# PMIC-MX8M.net
KiCad netlist of a schematic drawn in Altium Designer
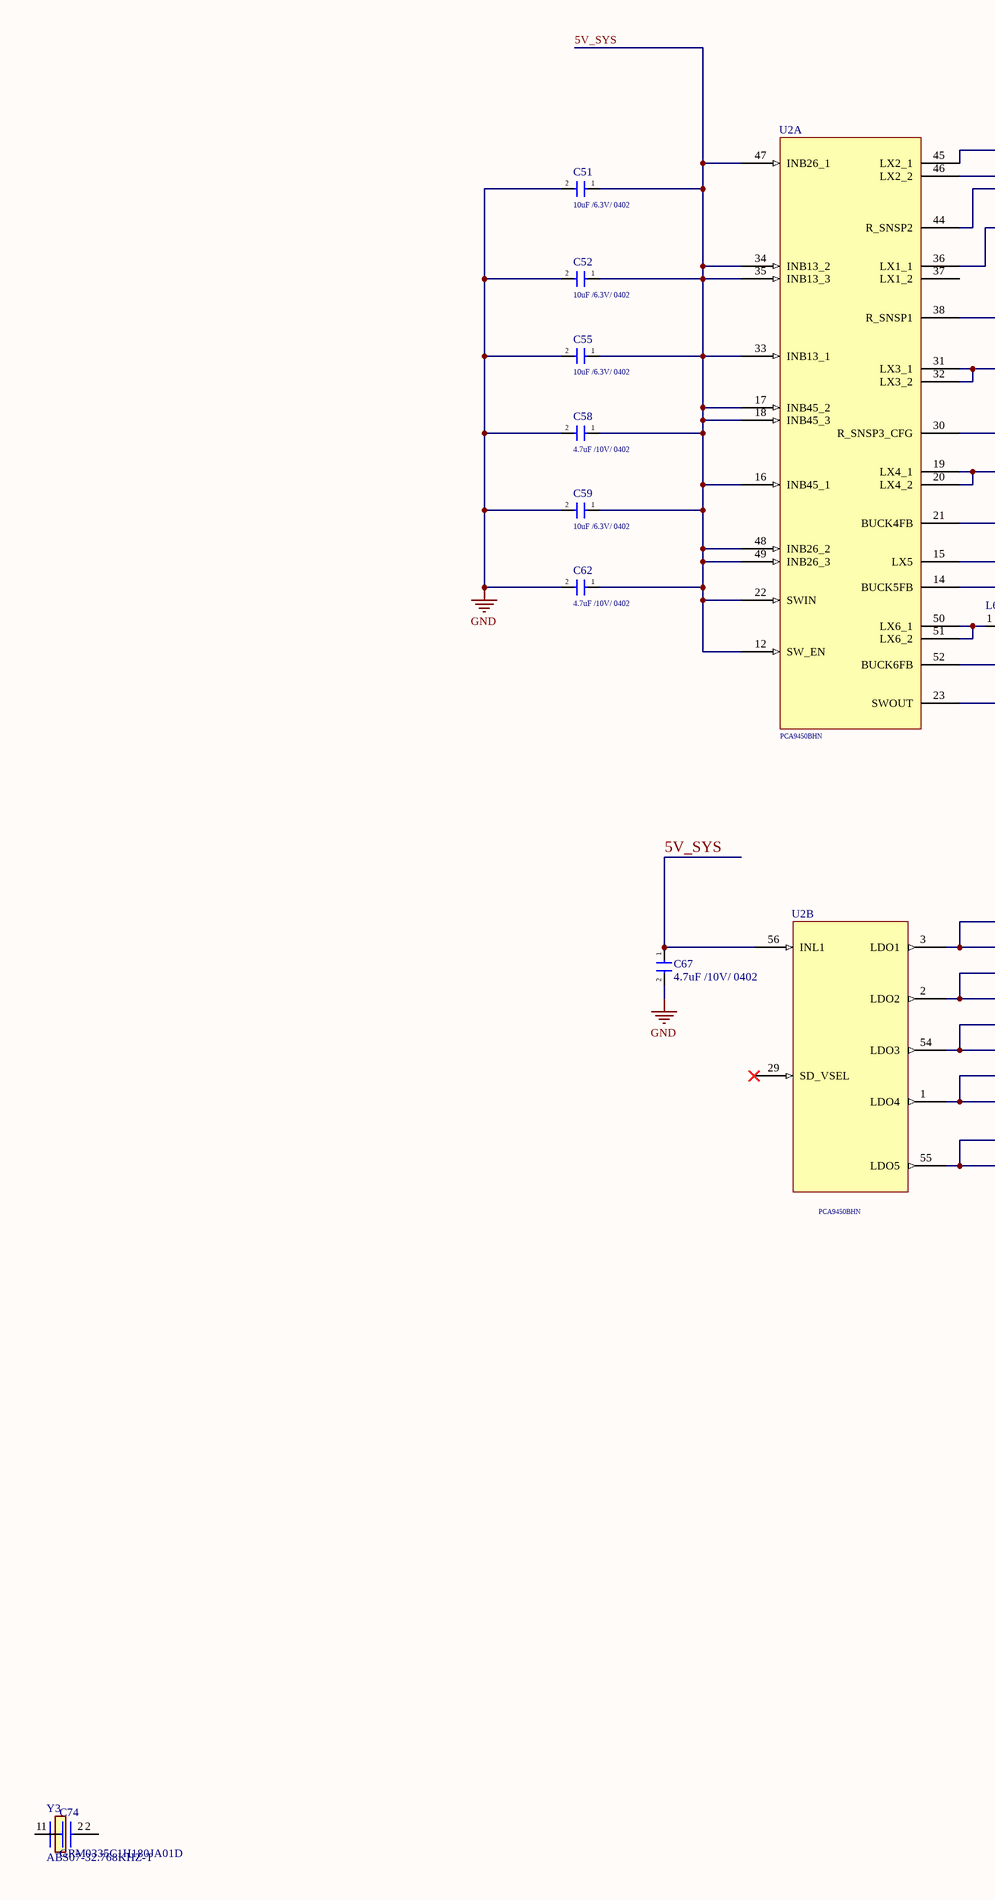
[diagram p0: PMIC-MX8M.SchDoc, left]
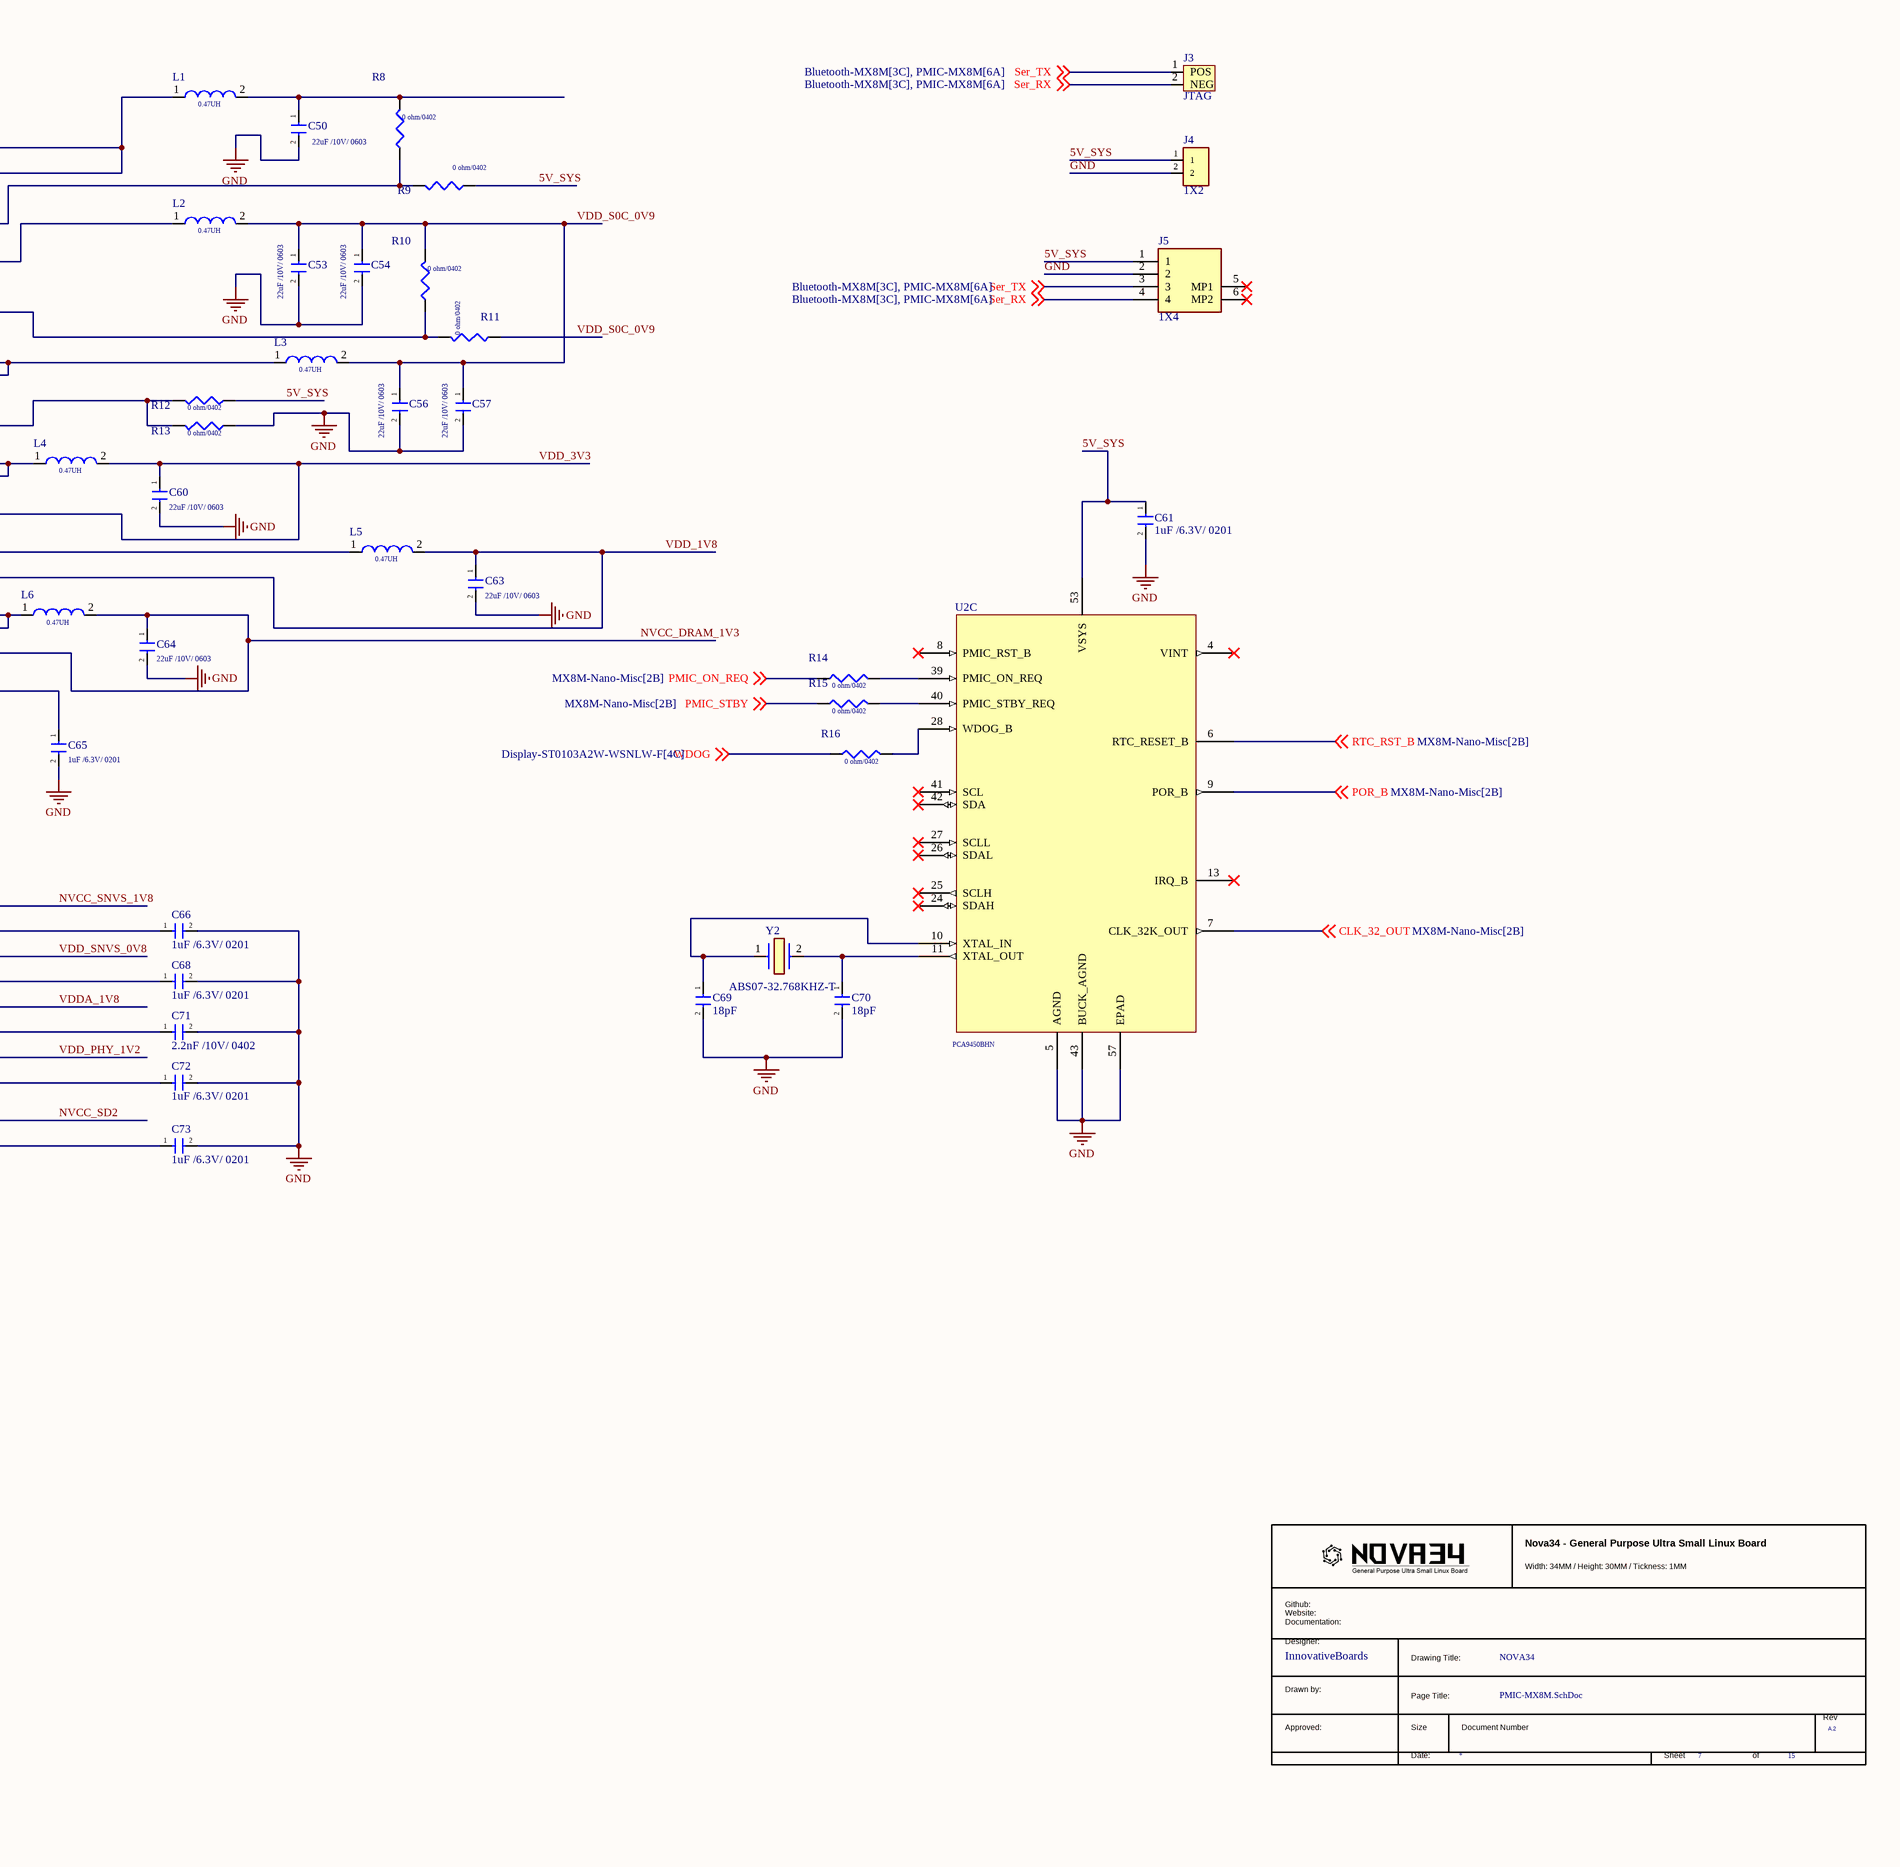
[diagram p1: PMIC-MX8M.SchDoc, right]

(export (version "E")
  (design (tool "Eeschema 10.0.6"))
  (components
    (comp (ref "C50")
      (value "22uF /10V/ 0603")
      (footprint "GRM18x")
      (description "Multilayer Ceramic Capacitors MLCC - SMD/SMT 22 uF 10 VDC 20% 0603 X5R")
      (fields
        (field (name "MANUFACTURER_PART_NUMBER") "GRM187R61A226ME15D")
        (field (name "MOUSER PART NUMBER") "81-GRM187R61A226ME5D")
      )
      (libsource (lib "Nova_SCHLIB") (part "GRM187R61A226ME15D"))
    )
    (comp (ref "C51")
      (value "10uF /6.3V/ 0402")
      (footprint "CAPC1005X65N")
      (description "Multilayer Ceramic Capacitors MLCC - SMD/SMT 10 uF 6.3 VDC 20% 0402 X5R")
      (fields
        (field (name "MANUFACTURER_PART_NUMBER") "GRM155R60J106ME15D")
        (field (name "MOUSER PART NUMBER") "81-GRM155R60J106ME5D")
      )
      (libsource (lib "Nova_SCHLIB") (part "GRM155R60J106ME15D"))
    )
    (comp (ref "C52")
      (value "10uF /6.3V/ 0402")
      (footprint "CAPC1005X65N")
      (description "Multilayer Ceramic Capacitors MLCC - SMD/SMT 10 uF 6.3 VDC 20% 0402 X5R")
      (fields
        (field (name "MANUFACTURER_PART_NUMBER") "GRM155R60J106ME15D")
        (field (name "MOUSER PART NUMBER") "81-GRM155R60J106ME5D")
      )
      (libsource (lib "Nova_SCHLIB") (part "GRM155R60J106ME15D"))
    )
    (comp (ref "C53")
      (value "22uF /10V/ 0603")
      (footprint "GRM18x")
      (description "Multilayer Ceramic Capacitors MLCC - SMD/SMT 22 uF 10 VDC 20% 0603 X5R")
      (fields
        (field (name "MANUFACTURER_PART_NUMBER") "GRM187R61A226ME15D")
        (field (name "MOUSER PART NUMBER") "81-GRM187R61A226ME5D")
      )
      (libsource (lib "Nova_SCHLIB") (part "GRM187R61A226ME15D"))
    )
    (comp (ref "C54")
      (value "22uF /10V/ 0603")
      (footprint "GRM18x")
      (description "Multilayer Ceramic Capacitors MLCC - SMD/SMT 22 uF 10 VDC 20% 0603 X5R")
      (fields
        (field (name "MANUFACTURER_PART_NUMBER") "GRM187R61A226ME15D")
        (field (name "MOUSER PART NUMBER") "81-GRM187R61A226ME5D")
      )
      (libsource (lib "Nova_SCHLIB") (part "GRM187R61A226ME15D"))
    )
    (comp (ref "C55")
      (value "10uF /6.3V/ 0402")
      (footprint "CAPC1005X65N")
      (description "Multilayer Ceramic Capacitors MLCC - SMD/SMT 10 uF 6.3 VDC 20% 0402 X5R")
      (fields
        (field (name "MANUFACTURER_PART_NUMBER") "GRM155R60J106ME15D")
        (field (name "MOUSER PART NUMBER") "81-GRM155R60J106ME5D")
      )
      (libsource (lib "Nova_SCHLIB") (part "GRM155R60J106ME15D"))
    )
    (comp (ref "C56")
      (value "22uF /10V/ 0603")
      (footprint "GRM18x")
      (description "Multilayer Ceramic Capacitors MLCC - SMD/SMT 22 uF 10 VDC 20% 0603 X5R")
      (fields
        (field (name "MANUFACTURER_PART_NUMBER") "GRM187R61A226ME15D")
        (field (name "MOUSER PART NUMBER") "81-GRM187R61A226ME5D")
      )
      (libsource (lib "Nova_SCHLIB") (part "GRM187R61A226ME15D"))
    )
    (comp (ref "C57")
      (value "22uF /10V/ 0603")
      (footprint "GRM18x")
      (description "Multilayer Ceramic Capacitors MLCC - SMD/SMT 22 uF 10 VDC 20% 0603 X5R")
      (fields
        (field (name "MANUFACTURER_PART_NUMBER") "GRM187R61A226ME15D")
        (field (name "MOUSER PART NUMBER") "81-GRM187R61A226ME5D")
      )
      (libsource (lib "Nova_SCHLIB") (part "GRM187R61A226ME15D"))
    )
    (comp (ref "C58")
      (value "4.7uF /10V/ 0402")
      (footprint "CAPC1005X70N")
      (description "Multilayer Ceramic Capacitors MLCC - SMD/SMT 0402 X6S 4.7 F 20 10VDC AEC-Q200")
      (fields
        (field (name "MANUFACTURER_PART_NUMBER") "GRT155C81A475ME13J")
        (field (name "MOUSER PART NUMBER") "81-GRT155C81A475ME3J")
      )
      (libsource (lib "Nova_SCHLIB") (part "GRT155C81A475ME13J"))
    )
    (comp (ref "C59")
      (value "10uF /6.3V/ 0402")
      (footprint "CAPC1005X65N")
      (description "Multilayer Ceramic Capacitors MLCC - SMD/SMT 10 uF 6.3 VDC 20% 0402 X5R")
      (fields
        (field (name "MANUFACTURER_PART_NUMBER") "GRM155R60J106ME15D")
        (field (name "MOUSER PART NUMBER") "81-GRM155R60J106ME5D")
      )
      (libsource (lib "Nova_SCHLIB") (part "GRM155R60J106ME15D"))
    )
    (comp (ref "C60")
      (value "22uF /10V/ 0603")
      (footprint "GRM18x")
      (description "Multilayer Ceramic Capacitors MLCC - SMD/SMT 22 uF 10 VDC 20% 0603 X5R")
      (fields
        (field (name "MANUFACTURER_PART_NUMBER") "GRM187R61A226ME15D")
        (field (name "MOUSER PART NUMBER") "81-GRM187R61A226ME5D")
      )
      (libsource (lib "Nova_SCHLIB") (part "GRM187R61A226ME15D"))
    )
    (comp (ref "C61")
      (value "1uF /6.3V/ 0201")
      (footprint "GRM033D70J224ME01D")
      (description "Multilayer Ceramic Capacitors MLCC - SMD/SMT 1 uF 6.3 VDC 20% 0201 X6S")
      (fields
        (field (name "MANUFACTURER_PART_NUMBER") "GRM033C80J105ME05J")
        (field (name "MOUSER PART NUMBER") "81-GRM033C80J105ME5J")
      )
      (libsource (lib "Nova_SCHLIB") (part "GRM033C80J105ME05J"))
    )
    (comp (ref "C62")
      (value "4.7uF /10V/ 0402")
      (footprint "CAPC1005X70N")
      (description "Multilayer Ceramic Capacitors MLCC - SMD/SMT 0402 X6S 4.7 F 20 10VDC AEC-Q200")
      (fields
        (field (name "MANUFACTURER_PART_NUMBER") "GRT155C81A475ME13J")
        (field (name "MOUSER PART NUMBER") "81-GRT155C81A475ME3J")
      )
      (libsource (lib "Nova_SCHLIB") (part "GRT155C81A475ME13J"))
    )
    (comp (ref "C63")
      (value "22uF /10V/ 0603")
      (footprint "GRM18x")
      (description "Multilayer Ceramic Capacitors MLCC - SMD/SMT 22 uF 10 VDC 20% 0603 X5R")
      (fields
        (field (name "MANUFACTURER_PART_NUMBER") "GRM187R61A226ME15D")
        (field (name "MOUSER PART NUMBER") "81-GRM187R61A226ME5D")
      )
      (libsource (lib "Nova_SCHLIB") (part "GRM187R61A226ME15D"))
    )
    (comp (ref "C64")
      (value "22uF /10V/ 0603")
      (footprint "GRM18x")
      (description "Multilayer Ceramic Capacitors MLCC - SMD/SMT 22 uF 10 VDC 20% 0603 X5R")
      (fields
        (field (name "MANUFACTURER_PART_NUMBER") "GRM187R61A226ME15D")
        (field (name "MOUSER PART NUMBER") "81-GRM187R61A226ME5D")
      )
      (libsource (lib "Nova_SCHLIB") (part "GRM187R61A226ME15D"))
    )
    (comp (ref "C65")
      (value "1uF /6.3V/ 0201")
      (footprint "GRM033D70J224ME01D")
      (description "Multilayer Ceramic Capacitors MLCC - SMD/SMT 1 uF 6.3 VDC 20% 0201 X6S")
      (fields
        (field (name "MANUFACTURER_PART_NUMBER") "GRM033C80J105ME05J")
        (field (name "MOUSER PART NUMBER") "81-GRM033C80J105ME5J")
      )
      (libsource (lib "Nova_SCHLIB") (part "GRM033C80J105ME05J"))
    )
    (comp (ref "C66")
      (value "1uF /6.3V/ 0201")
      (footprint "GRM033D70J224ME01D")
      (description "Multilayer Ceramic Capacitors MLCC - SMD/SMT 1 uF 6.3 VDC 20% 0201 X6S")
      (fields
        (field (name "MANUFACTURER_PART_NUMBER") "GRM033C80J105ME05J")
        (field (name "MOUSER PART NUMBER") "81-GRM033C80J105ME5J")
      )
      (libsource (lib "Nova_SCHLIB") (part "GRM033C80J105ME05J"))
    )
    (comp (ref "C67")
      (value "4.7uF /10V/ 0402")
      (footprint "CAPC1005X70N")
      (description "Multilayer Ceramic Capacitors MLCC - SMD/SMT 0402 X6S 4.7 F 20 10VDC AEC-Q200")
      (fields
        (field (name "MANUFACTURER_PART_NUMBER") "GRT155C81A475ME13J")
        (field (name "MOUSER PART NUMBER") "81-GRT155C81A475ME3J")
      )
      (libsource (lib "Nova_SCHLIB") (part "GRT155C81A475ME13J"))
    )
    (comp (ref "C68")
      (value "1uF /6.3V/ 0201")
      (footprint "GRM033D70J224ME01D")
      (description "Multilayer Ceramic Capacitors MLCC - SMD/SMT 1 uF 6.3 VDC 20% 0201 X6S")
      (fields
        (field (name "MANUFACTURER_PART_NUMBER") "GRM033C80J105ME05J")
        (field (name "MOUSER PART NUMBER") "81-GRM033C80J105ME5J")
      )
      (libsource (lib "Nova_SCHLIB") (part "GRM033C80J105ME05J"))
    )
    (comp (ref "C69")
      (value "18pF")
      (footprint "CAPC0603X33N")
      (description "Capacitor")
      (fields
        (field (name "MANUFACTURER_PART_NUMBER") "GRM0335C1H180JA01D")
        (field (name "MOUSER PART NUMBER") "81-GRM0335C1H180JA1D")
      )
      (libsource (lib "Nova_SCHLIB") (part "GRM0335C1H180JA01D"))
    )
    (comp (ref "C70")
      (value "18pF")
      (footprint "CAPC0603X33N")
      (description "Capacitor")
      (fields
        (field (name "MANUFACTURER_PART_NUMBER") "GRM0335C1H180JA01D")
        (field (name "MOUSER PART NUMBER") "81-GRM0335C1H180JA1D")
      )
      (libsource (lib "Nova_SCHLIB") (part "GRM0335C1H180JA01D"))
    )
    (comp (ref "C71")
      (value "2.2nF /10V/ 0402")
      (footprint "CAPC1005X70N")
      (description "Multilayer Ceramic Capacitors MLCC - SMD/SMT 2200 pF 10 VDC 10% 0402 X5R")
      (fields
        (field (name "MANUFACTURER_PART_NUMBER") "GRM155R61A222KA01D")
        (field (name "MOUSER PART NUMBER") "81-GRM155R61A222KA1D")
      )
      (libsource (lib "Nova_SCHLIB") (part "GRM155R61A222KA01D"))
    )
    (comp (ref "C72")
      (value "1uF /6.3V/ 0201")
      (footprint "GRM033D70J224ME01D")
      (description "Multilayer Ceramic Capacitors MLCC - SMD/SMT 1 uF 6.3 VDC 20% 0201 X6S")
      (fields
        (field (name "MANUFACTURER_PART_NUMBER") "GRM033C80J105ME05J")
        (field (name "MOUSER PART NUMBER") "81-GRM033C80J105ME5J")
      )
      (libsource (lib "Nova_SCHLIB") (part "GRM033C80J105ME05J"))
    )
    (comp (ref "C73")
      (value "1uF /6.3V/ 0201")
      (footprint "GRM033D70J224ME01D")
      (description "Multilayer Ceramic Capacitors MLCC - SMD/SMT 1 uF 6.3 VDC 20% 0201 X6S")
      (fields
        (field (name "MANUFACTURER_PART_NUMBER") "GRM033C80J105ME05J")
        (field (name "MOUSER PART NUMBER") "81-GRM033C80J105ME5J")
      )
      (libsource (lib "Nova_SCHLIB") (part "GRM033C80J105ME05J"))
    )
    (comp (ref "C74")
      (value "GRM0335C1H180JA01D")
      (footprint "SamacSys:CAPC0603X33N")
      (description "Capacitor")
      (fields (field (name "MOUSER PART NUMBER") "81-GRM0335C1H180JA1D"))
      (libsource (lib "*") (part "GRM0335C1H180JA01D"))
    )
    (comp (ref "J3") (value "JTAG") (footprint "JTAG") (libsource (lib "Nova_SCHLIB") (part "JTAG")))
    (comp (ref "J4")
      (value "1X2")
      (footprint "HDRV2W64P0X254_1X2_508X254X838P")
      (description "Connector")
      (fields
        (field (name "MANUFACTURER_PART_NUMBER") "TSW-102-07-G-S-002")
        (field (name "MOUSER PART NUMBER") "200-TSW-10207GS002")
      )
      (libsource (lib "Nova_SCHLIB") (part "TSW-102-07-G-S-002"))
    )
    (comp (ref "J5")
      (value "1X4")
      (footprint "B4BZRSM4TFLFSN")
      (description "Connector")
      (fields (field (name "MANUFACTURER_PART_NUMBER") "B4B-ZR-SM4-TF(LF)(SN)"))
      (libsource (lib "Nova_SCHLIB") (part "B4B-ZR-SM4-TF_LF__SN_"))
    )
    (comp (ref "L1")
      (value "0.47UH")
      (footprint "IND_SPH2520")
      (description "470 nH Shielded Drum Core, Wirewound Inductor 4.1 A 32mOhm Max 1008 (2520 Metric)")
      (fields (field (name "TOLERANCE") "20%"))
      (libsource (lib "Nova_SCHLIB") (part "WPN252012ER47MT"))
    )
    (comp (ref "L2")
      (value "0.47UH")
      (footprint "IND_SPH2520")
      (description "470 nH Shielded Drum Core, Wirewound Inductor 4.1 A 32mOhm Max 1008 (2520 Metric)")
      (fields (field (name "TOLERANCE") "20%"))
      (libsource (lib "Nova_SCHLIB") (part "WPN252012ER47MT"))
    )
    (comp (ref "L3")
      (value "0.47UH")
      (footprint "IND_SPH2520")
      (description "470 nH Shielded Drum Core, Wirewound Inductor 4.1 A 32mOhm Max 1008 (2520 Metric)")
      (fields (field (name "TOLERANCE") "20%"))
      (libsource (lib "Nova_SCHLIB") (part "WPN252012ER47MT"))
    )
    (comp (ref "L4")
      (value "0.47UH")
      (footprint "IND_SPH2520")
      (description "470 nH Shielded Drum Core, Wirewound Inductor 4.1 A 32mOhm Max 1008 (2520 Metric)")
      (fields (field (name "TOLERANCE") "20%"))
      (libsource (lib "Nova_SCHLIB") (part "WPN252012ER47MT"))
    )
    (comp (ref "L5")
      (value "0.47UH")
      (footprint "IND_SPH2520")
      (description "470 nH Shielded Drum Core, Wirewound Inductor 4.1 A 32mOhm Max 1008 (2520 Metric)")
      (fields (field (name "TOLERANCE") "20%"))
      (libsource (lib "Nova_SCHLIB") (part "WPN252012ER47MT"))
    )
    (comp (ref "L6")
      (value "0.47UH")
      (footprint "IND_SPH2520")
      (description "470 nH Shielded Drum Core, Wirewound Inductor 4.1 A 32mOhm Max 1008 (2520 Metric)")
      (fields (field (name "TOLERANCE") "20%"))
      (libsource (lib "Nova_SCHLIB") (part "WPN252012ER47MT"))
    )
    (comp (ref "R8")
      (value "0 ohm/0402")
      (footprint "RES_0402")
      (description "RES MF ZERO OHM 1/16W 5% 0402")
      (fields (field (name "TOLERANCE") "5%") (field (name "VOLTAGE") "1/16W"))
      (libsource (lib "Nova_SCHLIB") (part "RC0402JR-070RL"))
    )
    (comp (ref "R9")
      (value "0 ohm/0402")
      (footprint "RES_0402")
      (description "RES MF ZERO OHM 1/16W 5% 0402")
      (fields (field (name "TOLERANCE") "5%") (field (name "VOLTAGE") "1/16W"))
      (libsource (lib "Nova_SCHLIB") (part "RC0402JR-070RL"))
    )
    (comp (ref "R10")
      (value "0 ohm/0402")
      (footprint "RES_0402")
      (description "RES MF ZERO OHM 1/16W 5% 0402")
      (fields (field (name "TOLERANCE") "5%") (field (name "VOLTAGE") "1/16W"))
      (libsource (lib "Nova_SCHLIB") (part "RC0402JR-070RL"))
    )
    (comp (ref "R11")
      (value "0 ohm/0402")
      (footprint "RES_0402")
      (description "RES MF ZERO OHM 1/16W 5% 0402")
      (fields (field (name "TOLERANCE") "5%") (field (name "VOLTAGE") "1/16W"))
      (libsource (lib "Nova_SCHLIB") (part "RC0402JR-070RL"))
    )
    (comp (ref "R12")
      (value "0 ohm/0402")
      (footprint "RES_0402")
      (description "RES MF ZERO OHM 1/16W 5% 0402")
      (fields (field (name "TOLERANCE") "5%") (field (name "VOLTAGE") "1/16W"))
      (libsource (lib "Nova_SCHLIB") (part "RC0402JR-070RL"))
    )
    (comp (ref "R13")
      (value "0 ohm/0402")
      (footprint "RES_0402")
      (description "RES MF ZERO OHM 1/16W 5% 0402")
      (fields (field (name "TOLERANCE") "5%") (field (name "VOLTAGE") "1/16W"))
      (libsource (lib "Nova_SCHLIB") (part "RC0402JR-070RL"))
    )
    (comp (ref "R14")
      (value "0 ohm/0402")
      (footprint "RES_0402")
      (description "RES MF ZERO OHM 1/16W 5% 0402")
      (fields (field (name "TOLERANCE") "5%") (field (name "VOLTAGE") "1/16W"))
      (libsource (lib "Nova_SCHLIB") (part "RC0402JR-070RL"))
    )
    (comp (ref "R15")
      (value "0 ohm/0402")
      (footprint "RES_0402")
      (description "RES MF ZERO OHM 1/16W 5% 0402")
      (fields (field (name "TOLERANCE") "5%") (field (name "VOLTAGE") "1/16W"))
      (libsource (lib "Nova_SCHLIB") (part "RC0402JR-070RL"))
    )
    (comp (ref "R16")
      (value "0 ohm/0402")
      (footprint "RES_0402")
      (description "RES MF ZERO OHM 1/16W 5% 0402")
      (fields (field (name "TOLERANCE") "5%") (field (name "VOLTAGE") "1/16W"))
      (libsource (lib "Nova_SCHLIB") (part "RC0402JR-070RL"))
    )
    (comp (ref "U2")
      (value "PCA9450BHN")
      (footprint "QFN40P700X700X100-57N-D")
      (description "IC POWER MANAGEMENT 2.7-5.5V HVQFN56")
      (fields (field (name "VOLTAGE") "2.7-5.5V"))
      (libsource (lib "Nova_SCHLIB") (part "PCA9450_HVQFN56P_A"))
    )
    (comp (ref "Y2")
      (value "ABS07-32.768KHZ-T")
      (footprint "ABS07")
      (description "Crystal or Oscillator")
      (fields (field (name "MOUSER PART NUMBER") "815-ABS07-32.768KHZT"))
      (libsource (lib "Nova_SCHLIB") (part "ABS07-32.768KHZ-T"))
    )
    (comp (ref "Y3")
      (value "ABS07-32.768KHZ-T")
      (footprint "SamacSys:ABS07")
      (description "Crystal or Oscillator")
      (fields (field (name "MOUSER PART NUMBER") "815-ABS07-32.768KHZT"))
      (libsource (lib "*") (part "ABS07-32.768KHZ-T"))
    )
  )
  (nets
    (net (code "1") (name "/5V_SYS") (class "Default")
      (node (ref "C51") (pin "1") (pinfunction "1_1") (pintype "passive"))
      (node (ref "C52") (pin "1") (pinfunction "1_1") (pintype "passive"))
      (node (ref "C55") (pin "1") (pinfunction "1_1") (pintype "passive"))
      (node (ref "C58") (pin "1") (pinfunction "1_1") (pintype "passive"))
      (node (ref "C59") (pin "1") (pinfunction "1_1") (pintype "passive"))
      (node (ref "C61") (pin "1") (pinfunction "1_1") (pintype "passive"))
      (node (ref "C62") (pin "1") (pinfunction "1_1") (pintype "passive"))
      (node (ref "C67") (pin "1") (pinfunction "1_1") (pintype "passive"))
      (node (ref "J4") (pin "1") (pinfunction "1_1") (pintype "passive"))
      (node (ref "J5") (pin "1") (pinfunction "1_1") (pintype "passive"))
      (node (ref "R12") (pin "1") (pinfunction "1_1") (pintype "passive"))
      (node (ref "R9") (pin "1") (pinfunction "1_1") (pintype "passive"))
      (node (ref "U2") (pin "12") (pinfunction "SW_EN_12") (pintype "input"))
      (node (ref "U2") (pin "16") (pinfunction "INB45_1_16") (pintype "input"))
      (node (ref "U2") (pin "17") (pinfunction "INB45_2_17") (pintype "input"))
      (node (ref "U2") (pin "18") (pinfunction "INB45_3_18") (pintype "input"))
      (node (ref "U2") (pin "22") (pinfunction "SWIN_22") (pintype "input"))
      (node (ref "U2") (pin "33") (pinfunction "INB13_1_33") (pintype "input"))
      (node (ref "U2") (pin "34") (pinfunction "INB13_2_34") (pintype "input"))
      (node (ref "U2") (pin "35") (pinfunction "INB13_3_35") (pintype "input"))
      (node (ref "U2") (pin "47") (pinfunction "INB26_1_47") (pintype "input"))
      (node (ref "U2") (pin "48") (pinfunction "INB26_2_48") (pintype "input"))
      (node (ref "U2") (pin "49") (pinfunction "INB26_3_49") (pintype "input"))
      (node (ref "U2") (pin "53") (pinfunction "VSYS_53") (pintype "power_in"))
      (node (ref "U2") (pin "56") (pinfunction "INL1_56") (pintype "input"))
    )
    (net (code "2") (name "/NVCC_DRAM_1V3") (class "Default")
      (node (ref "C64") (pin "1") (pinfunction "1_1") (pintype "passive"))
      (node (ref "L6") (pin "2") (pinfunction "2_2") (pintype "passive"))
      (node (ref "U2") (pin "52") (pinfunction "BUCK6FB_52") (pintype "passive"))
    )
    (net (code "3") (name "/NVCC_SD2") (class "Default")
      (node (ref "C73") (pin "1") (pinfunction "1_1") (pintype "passive"))
      (node (ref "U2") (pin "55") (pinfunction "LDO5_55") (pintype "output"))
    )
    (net (code "4") (name "/NVCC_SNVS_1V8") (class "Default")
      (node (ref "C66") (pin "1") (pinfunction "1_1") (pintype "passive"))
      (node (ref "U2") (pin "3") (pinfunction "LDO1_3") (pintype "output"))
    )
    (net (code "5") (name "/VDDA_1V8") (class "Default")
      (node (ref "C71") (pin "1") (pinfunction "1_1") (pintype "passive"))
      (node (ref "U2") (pin "54") (pinfunction "LDO3_54") (pintype "output"))
    )
    (net (code "6") (name "/VDD_1V8") (class "Default")
      (node (ref "C63") (pin "1") (pinfunction "1_1") (pintype "passive"))
      (node (ref "L5") (pin "2") (pinfunction "2_2") (pintype "passive"))
      (node (ref "U2") (pin "14") (pinfunction "BUCK5FB_14") (pintype "passive"))
    )
    (net (code "7") (name "/VDD_3V3") (class "Default")
      (node (ref "C60") (pin "1") (pinfunction "1_1") (pintype "passive"))
      (node (ref "L4") (pin "2") (pinfunction "2_2") (pintype "passive"))
      (node (ref "U2") (pin "21") (pinfunction "BUCK4FB_21") (pintype "passive"))
    )
    (net (code "8") (name "/VDD_PHY_1V2") (class "Default")
      (node (ref "C72") (pin "1") (pinfunction "1_1") (pintype "passive"))
      (node (ref "U2") (pin "1") (pinfunction "LDO4_1") (pintype "output"))
    )
    (net (code "9") (name "/VDD_S0C_0V9") (class "Default")
      (node (ref "C53") (pin "1") (pinfunction "1_1") (pintype "passive"))
      (node (ref "C54") (pin "1") (pinfunction "1_1") (pintype "passive"))
      (node (ref "C56") (pin "1") (pinfunction "1_1") (pintype "passive"))
      (node (ref "C57") (pin "1") (pinfunction "1_1") (pintype "passive"))
      (node (ref "L2") (pin "2") (pinfunction "2_2") (pintype "passive"))
      (node (ref "L3") (pin "2") (pinfunction "2_2") (pintype "passive"))
      (node (ref "R10") (pin "2") (pinfunction "2_2") (pintype "passive"))
      (node (ref "R11") (pin "1") (pinfunction "1_1") (pintype "passive"))
    )
    (net (code "10") (name "/VDD_SNVS_0V8") (class "Default")
      (node (ref "C68") (pin "1") (pinfunction "1_1") (pintype "passive"))
      (node (ref "U2") (pin "2") (pinfunction "LDO2_2") (pintype "output"))
    )
    (net (code "11") (name "CLK_32_OUT") (class "Default")
      (node (ref "U2") (pin "7") (pinfunction "CLK_32K_OUT_7") (pintype "output"))
    )
    (net (code "12") (name "GND") (class "Default")
      (node (ref "C50") (pin "2") (pinfunction "2_2") (pintype "passive"))
      (node (ref "C51") (pin "2") (pinfunction "2_2") (pintype "passive"))
      (node (ref "C52") (pin "2") (pinfunction "2_2") (pintype "passive"))
      (node (ref "C53") (pin "2") (pinfunction "2_2") (pintype "passive"))
      (node (ref "C54") (pin "2") (pinfunction "2_2") (pintype "passive"))
      (node (ref "C55") (pin "2") (pinfunction "2_2") (pintype "passive"))
      (node (ref "C56") (pin "2") (pinfunction "2_2") (pintype "passive"))
      (node (ref "C57") (pin "2") (pinfunction "2_2") (pintype "passive"))
      (node (ref "C58") (pin "2") (pinfunction "2_2") (pintype "passive"))
      (node (ref "C59") (pin "2") (pinfunction "2_2") (pintype "passive"))
      (node (ref "C60") (pin "2") (pinfunction "2_2") (pintype "passive"))
      (node (ref "C61") (pin "2") (pinfunction "2_2") (pintype "passive"))
      (node (ref "C62") (pin "2") (pinfunction "2_2") (pintype "passive"))
      (node (ref "C63") (pin "2") (pinfunction "2_2") (pintype "passive"))
      (node (ref "C64") (pin "2") (pinfunction "2_2") (pintype "passive"))
      (node (ref "C65") (pin "2") (pinfunction "2_2") (pintype "passive"))
      (node (ref "C66") (pin "2") (pinfunction "2_2") (pintype "passive"))
      (node (ref "C67") (pin "2") (pinfunction "2_2") (pintype "passive"))
      (node (ref "C68") (pin "2") (pinfunction "2_2") (pintype "passive"))
      (node (ref "C69") (pin "2") (pinfunction "2_2") (pintype "passive"))
      (node (ref "C70") (pin "2") (pinfunction "2_2") (pintype "passive"))
      (node (ref "C71") (pin "2") (pinfunction "2_2") (pintype "passive"))
      (node (ref "C72") (pin "2") (pinfunction "2_2") (pintype "passive"))
      (node (ref "C73") (pin "2") (pinfunction "2_2") (pintype "passive"))
      (node (ref "J4") (pin "2") (pinfunction "2_2") (pintype "passive"))
      (node (ref "J5") (pin "2") (pinfunction "2_2") (pintype "passive"))
      (node (ref "R13") (pin "1") (pinfunction "1_1") (pintype "passive"))
      (node (ref "U2") (pin "43") (pinfunction "BUCK_AGND_43") (pintype "power_in"))
      (node (ref "U2") (pin "5") (pinfunction "AGND_5") (pintype "power_in"))
      (node (ref "U2") (pin "57") (pinfunction "EPAD_57") (pintype "power_in"))
    )
    (net (code "13") (name "Net-(C50-Pad1)") (class "Default")
      (node (ref "C50") (pin "1") (pinfunction "1_1") (pintype "passive"))
      (node (ref "L1") (pin "2") (pinfunction "2_2") (pintype "passive"))
      (node (ref "R8") (pin "2") (pinfunction "2_2") (pintype "passive"))
    )
    (net (code "14") (name "Net-(C74-Pad1)") (class "Default")
      (node (ref "C74") (pin "1") (pinfunction "1_1") (pintype "passive"))
      (node (ref "Y3") (pin "1") (pinfunction "1_1") (pintype "passive"))
    )
    (net (code "15") (name "Net-(U2A-LX1_1)") (class "Default")
      (node (ref "L2") (pin "1") (pinfunction "1_1") (pintype "passive"))
      (node (ref "U2") (pin "36") (pinfunction "LX1_1_36") (pintype "passive"))
    )
    (net (code "16") (name "Net-(U2A-LX2_1)") (class "Default")
      (node (ref "L1") (pin "1") (pinfunction "1_1") (pintype "passive"))
      (node (ref "U2") (pin "45") (pinfunction "LX2_1_45") (pintype "passive"))
      (node (ref "U2") (pin "46") (pinfunction "LX2_2_46") (pintype "passive"))
    )
    (net (code "17") (name "Net-(U2A-LX3_1)") (class "Default")
      (node (ref "L3") (pin "1") (pinfunction "1_1") (pintype "passive"))
      (node (ref "U2") (pin "31") (pinfunction "LX3_1_31") (pintype "passive"))
      (node (ref "U2") (pin "32") (pinfunction "LX3_2_32") (pintype "passive"))
    )
    (net (code "18") (name "Net-(U2A-LX4_1)") (class "Default")
      (node (ref "L4") (pin "1") (pinfunction "1_1") (pintype "passive"))
      (node (ref "U2") (pin "19") (pinfunction "LX4_1_19") (pintype "passive"))
      (node (ref "U2") (pin "20") (pinfunction "LX4_2_20") (pintype "passive"))
    )
    (net (code "19") (name "Net-(U2A-LX5)") (class "Default")
      (node (ref "L5") (pin "1") (pinfunction "1_1") (pintype "passive"))
      (node (ref "U2") (pin "15") (pinfunction "LX5_15") (pintype "passive"))
    )
    (net (code "20") (name "Net-(U2A-LX6_1)") (class "Default")
      (node (ref "L6") (pin "1") (pinfunction "1_1") (pintype "passive"))
      (node (ref "U2") (pin "50") (pinfunction "LX6_1_50") (pintype "passive"))
      (node (ref "U2") (pin "51") (pinfunction "LX6_2_51") (pintype "passive"))
    )
    (net (code "21") (name "Net-(U2A-R_SNSP1)") (class "Default")
      (node (ref "R10") (pin "1") (pinfunction "1_1") (pintype "passive"))
      (node (ref "R11") (pin "2") (pinfunction "2_2") (pintype "passive"))
      (node (ref "U2") (pin "38") (pinfunction "R_SNSP1_38") (pintype "passive"))
    )
    (net (code "22") (name "Net-(U2A-R_SNSP2)") (class "Default")
      (node (ref "R8") (pin "1") (pinfunction "1_1") (pintype "passive"))
      (node (ref "R9") (pin "2") (pinfunction "2_2") (pintype "passive"))
      (node (ref "U2") (pin "44") (pinfunction "R_SNSP2_44") (pintype "passive"))
    )
    (net (code "23") (name "Net-(U2A-R_SNSP3_CFG)") (class "Default")
      (node (ref "R12") (pin "2") (pinfunction "2_2") (pintype "passive"))
      (node (ref "R13") (pin "2") (pinfunction "2_2") (pintype "passive"))
      (node (ref "U2") (pin "30") (pinfunction "R_SNSP3_CFG_30") (pintype "passive"))
    )
    (net (code "24") (name "Net-(U2A-SWOUT)") (class "Default")
      (node (ref "C65") (pin "1") (pinfunction "1_1") (pintype "passive"))
      (node (ref "U2") (pin "23") (pinfunction "SWOUT_23") (pintype "passive"))
    )
    (net (code "25") (name "Net-(U2C-PMIC_ON_REQ)") (class "Default")
      (node (ref "R14") (pin "2") (pinfunction "2_2") (pintype "passive"))
      (node (ref "U2") (pin "39") (pinfunction "PMIC_ON_REQ_39") (pintype "input"))
    )
    (net (code "26") (name "Net-(U2C-PMIC_STBY_REQ)") (class "Default")
      (node (ref "R15") (pin "2") (pinfunction "2_2") (pintype "passive"))
      (node (ref "U2") (pin "40") (pinfunction "PMIC_STBY_REQ_40") (pintype "input"))
    )
    (net (code "27") (name "Net-(U2C-WDOG_B)") (class "Default")
      (node (ref "R16") (pin "2") (pinfunction "2_2") (pintype "passive"))
      (node (ref "U2") (pin "28") (pinfunction "WDOG_B_28") (pintype "input"))
    )
    (net (code "28") (name "Net-(U2C-XTAL_IN)") (class "Default")
      (node (ref "C69") (pin "1") (pinfunction "1_1") (pintype "passive"))
      (node (ref "U2") (pin "10") (pinfunction "XTAL_IN_10") (pintype "input"))
      (node (ref "Y2") (pin "1") (pinfunction "1_1") (pintype "passive"))
    )
    (net (code "29") (name "Net-(U2C-XTAL_OUT)") (class "Default")
      (node (ref "C70") (pin "1") (pinfunction "1_1") (pintype "passive"))
      (node (ref "U2") (pin "11") (pinfunction "XTAL_OUT_11") (pintype "output"))
      (node (ref "Y2") (pin "2") (pinfunction "2_2") (pintype "passive"))
    )
    (net (code "30") (name "PMIC_ON_REQ") (class "Default")
      (node (ref "R14") (pin "1") (pinfunction "1_1") (pintype "passive"))
    )
    (net (code "31") (name "PMIC_STBY") (class "Default")
      (node (ref "R15") (pin "1") (pinfunction "1_1") (pintype "passive"))
    )
    (net (code "32") (name "POR_B") (class "Default")
      (node (ref "U2") (pin "9") (pinfunction "POR_B_9") (pintype "output"))
    )
    (net (code "33") (name "RTC_RST_B") (class "Default")
      (node (ref "U2") (pin "6") (pinfunction "RTC_RESET_B_6") (pintype "open_collector"))
    )
    (net (code "34") (name "Ser_RX") (class "Default")
      (node (ref "J3") (pin "2") (pinfunction "NEG_2") (pintype "passive"))
      (node (ref "J5") (pin "4") (pinfunction "4_4") (pintype "passive"))
    )
    (net (code "35") (name "Ser_TX") (class "Default")
      (node (ref "J3") (pin "1") (pinfunction "POS_1") (pintype "passive"))
      (node (ref "J5") (pin "3") (pinfunction "3_3") (pintype "passive"))
    )
    (net (code "36") (name "WDOG") (class "Default")
      (node (ref "R16") (pin "1") (pinfunction "1_1") (pintype "passive"))
    )
    (net (code "37") (name "unconnected-(C74-Pad2)") (class "Default")
      (node (ref "C74") (pin "2") (pinfunction "2_2") (pintype "passive"))
    )
    (net (code "38") (name "unconnected-(J5-MP1-Pad5)") (class "Default")
      (node (ref "J5") (pin "5") (pinfunction "MP1_5") (pintype "passive+no_connect"))
    )
    (net (code "39") (name "unconnected-(J5-MP2-Pad6)") (class "Default")
      (node (ref "J5") (pin "6") (pinfunction "MP2_6") (pintype "passive+no_connect"))
    )
    (net (code "40") (name "unconnected-(U2A-LX1_2-Pad37)") (class "Default")
      (node (ref "U2") (pin "37") (pinfunction "LX1_2_37") (pintype "passive"))
    )
    (net (code "41") (name "unconnected-(U2B-SD_VSEL-Pad29)") (class "Default")
      (node (ref "U2") (pin "29") (pinfunction "SD_VSEL_29") (pintype "input+no_connect"))
    )
    (net (code "42") (name "unconnected-(U2C-IRQ_B-Pad13)") (class "Default")
      (node (ref "U2") (pin "13") (pinfunction "IRQ_B_13") (pintype "open_collector+no_connect"))
    )
    (net (code "43") (name "unconnected-(U2C-PMIC_RST_B-Pad8)") (class "Default")
      (node (ref "U2") (pin "8") (pinfunction "PMIC_RST_B_8") (pintype "input+no_connect"))
    )
    (net (code "44") (name "unconnected-(U2C-SCL-Pad41)") (class "Default")
      (node (ref "U2") (pin "41") (pinfunction "SCL_41") (pintype "input+no_connect"))
    )
    (net (code "45") (name "unconnected-(U2C-SCLH-Pad25)") (class "Default")
      (node (ref "U2") (pin "25") (pinfunction "SCLH_25") (pintype "output+no_connect"))
    )
    (net (code "46") (name "unconnected-(U2C-SCLL-Pad27)") (class "Default")
      (node (ref "U2") (pin "27") (pinfunction "SCLL_27") (pintype "input+no_connect"))
    )
    (net (code "47") (name "unconnected-(U2C-SDA-Pad42)") (class "Default")
      (node (ref "U2") (pin "42") (pinfunction "SDA_42") (pintype "bidirectional+no_connect"))
    )
    (net (code "48") (name "unconnected-(U2C-SDAH-Pad24)") (class "Default")
      (node (ref "U2") (pin "24") (pinfunction "SDAH_24") (pintype "bidirectional+no_connect"))
    )
    (net (code "49") (name "unconnected-(U2C-SDAL-Pad26)") (class "Default")
      (node (ref "U2") (pin "26") (pinfunction "SDAL_26") (pintype "bidirectional+no_connect"))
    )
    (net (code "50") (name "unconnected-(U2C-VINT-Pad4)") (class "Default")
      (node (ref "U2") (pin "4") (pinfunction "VINT_4") (pintype "output+no_connect"))
    )
    (net (code "51") (name "unconnected-(Y3-Pad2)") (class "Default")
      (node (ref "Y3") (pin "2") (pinfunction "2_2") (pintype "passive"))
    )
  )
)
